# power_supply.net
KiCad netlist of a schematic drawn in Altium Designer
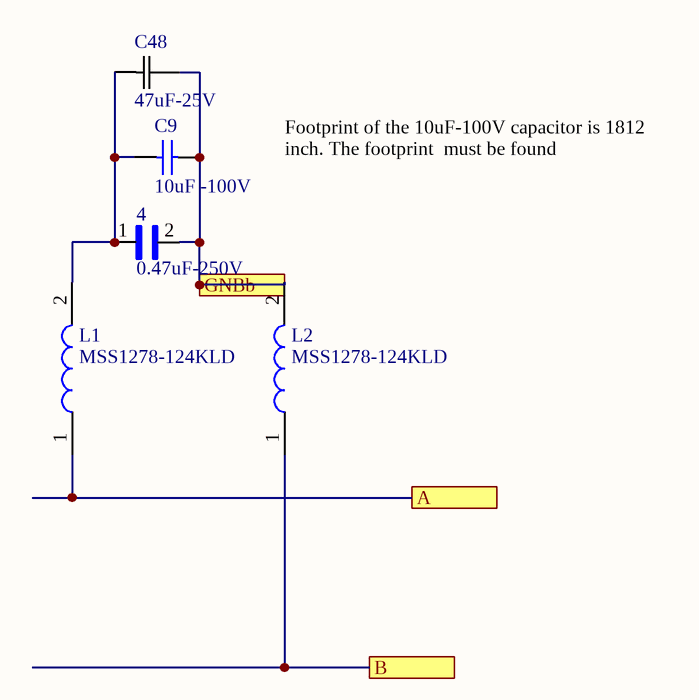
[diagram p0: power_supply.SchDoc]

(export (version "E")
  (design (tool "Eeschema 10.0.6"))
  (components
    (comp (ref "4")
      (value "0.47uF-250V")
      (footprint "CAPC3326X280N")
      (fields
        (field (name "MP") "C1210X474KARACAUTO")
        (field (name "MF") "{'manufacturer': u'KEMET'}")
        (field (name "SOURCE") "workerBoard.SCHLIB")
      )
      (libsource (lib "GIGUL") (part "C1210X474KARACAUTO"))
    )
    (comp (ref "C9")
      (value "10uF -100V")
      (description "Capacitor")
      (fields (field (name "Comment") "Symbol") (field (name "SOURCE") "workerBoard.SCHLIB"))
      (libsource (lib "GIGUL") (part "Symbol"))
    )
    (comp (ref "C48")
      (value "47uF-25V")
      (description "No Description Available")
      (fields
        (field (name "MANUFACTURER_PART_NUMBER") "GRM31CR61E476ME44K")
        (field (name "COPYRIGHT") "Copyright (C) 2021 Ultra Librarian. All rights reserved.")
        (field (name "SOURCE") "workerBoard.SCHLIB")
      )
      (libsource (lib "GIGUL") (part "GRM31CR61E476ME44K"))
    )
    (comp (ref "L1")
      (value "MSS1278-124KLD")
      (footprint "INDPM120120X805N")
      (description "Inductor")
      (fields (field (name "SOURCE") "workerBoard.SCHLIB"))
      (libsource (lib "GIGUL") (part "MSS1278-124KLD"))
    )
    (comp (ref "L2")
      (value "MSS1278-124KLD")
      (footprint "INDPM120120X805N")
      (description "Inductor")
      (fields (field (name "SOURCE") "workerBoard.SCHLIB"))
      (libsource (lib "GIGUL") (part "MSS1278-124KLD"))
    )
  )
  (nets
    (net (code "1") (name "/A") (class "Default")
      (node (ref "L1") (pin "1") (pinfunction "1_1") (pintype "passive"))
    )
    (net (code "2") (name "/B") (class "Default")
      (node (ref "L2") (pin "1") (pinfunction "1_1") (pintype "passive"))
    )
    (net (code "3") (name "/GNBb") (class "Default")
      (node (ref "4") (pin "2") (pinfunction "2_2") (pintype "passive"))
      (node (ref "C48") (pin "2") (pinfunction "2_2") (pintype "passive"))
      (node (ref "C9") (pin "2") (pinfunction "2_2") (pintype "passive"))
      (node (ref "L2") (pin "2") (pinfunction "2_2") (pintype "passive"))
    )
    (net (code "4") (name "Net-(4-Pad1)") (class "Default")
      (node (ref "4") (pin "1") (pinfunction "1_1") (pintype "passive"))
      (node (ref "C48") (pin "1") (pinfunction "1_1") (pintype "passive"))
      (node (ref "C9") (pin "1") (pinfunction "1_1") (pintype "passive"))
      (node (ref "L1") (pin "2") (pinfunction "2_2") (pintype "passive"))
    )
  )
)
